# Sheet1.net
KiCad netlist of a schematic drawn in Altium Designer
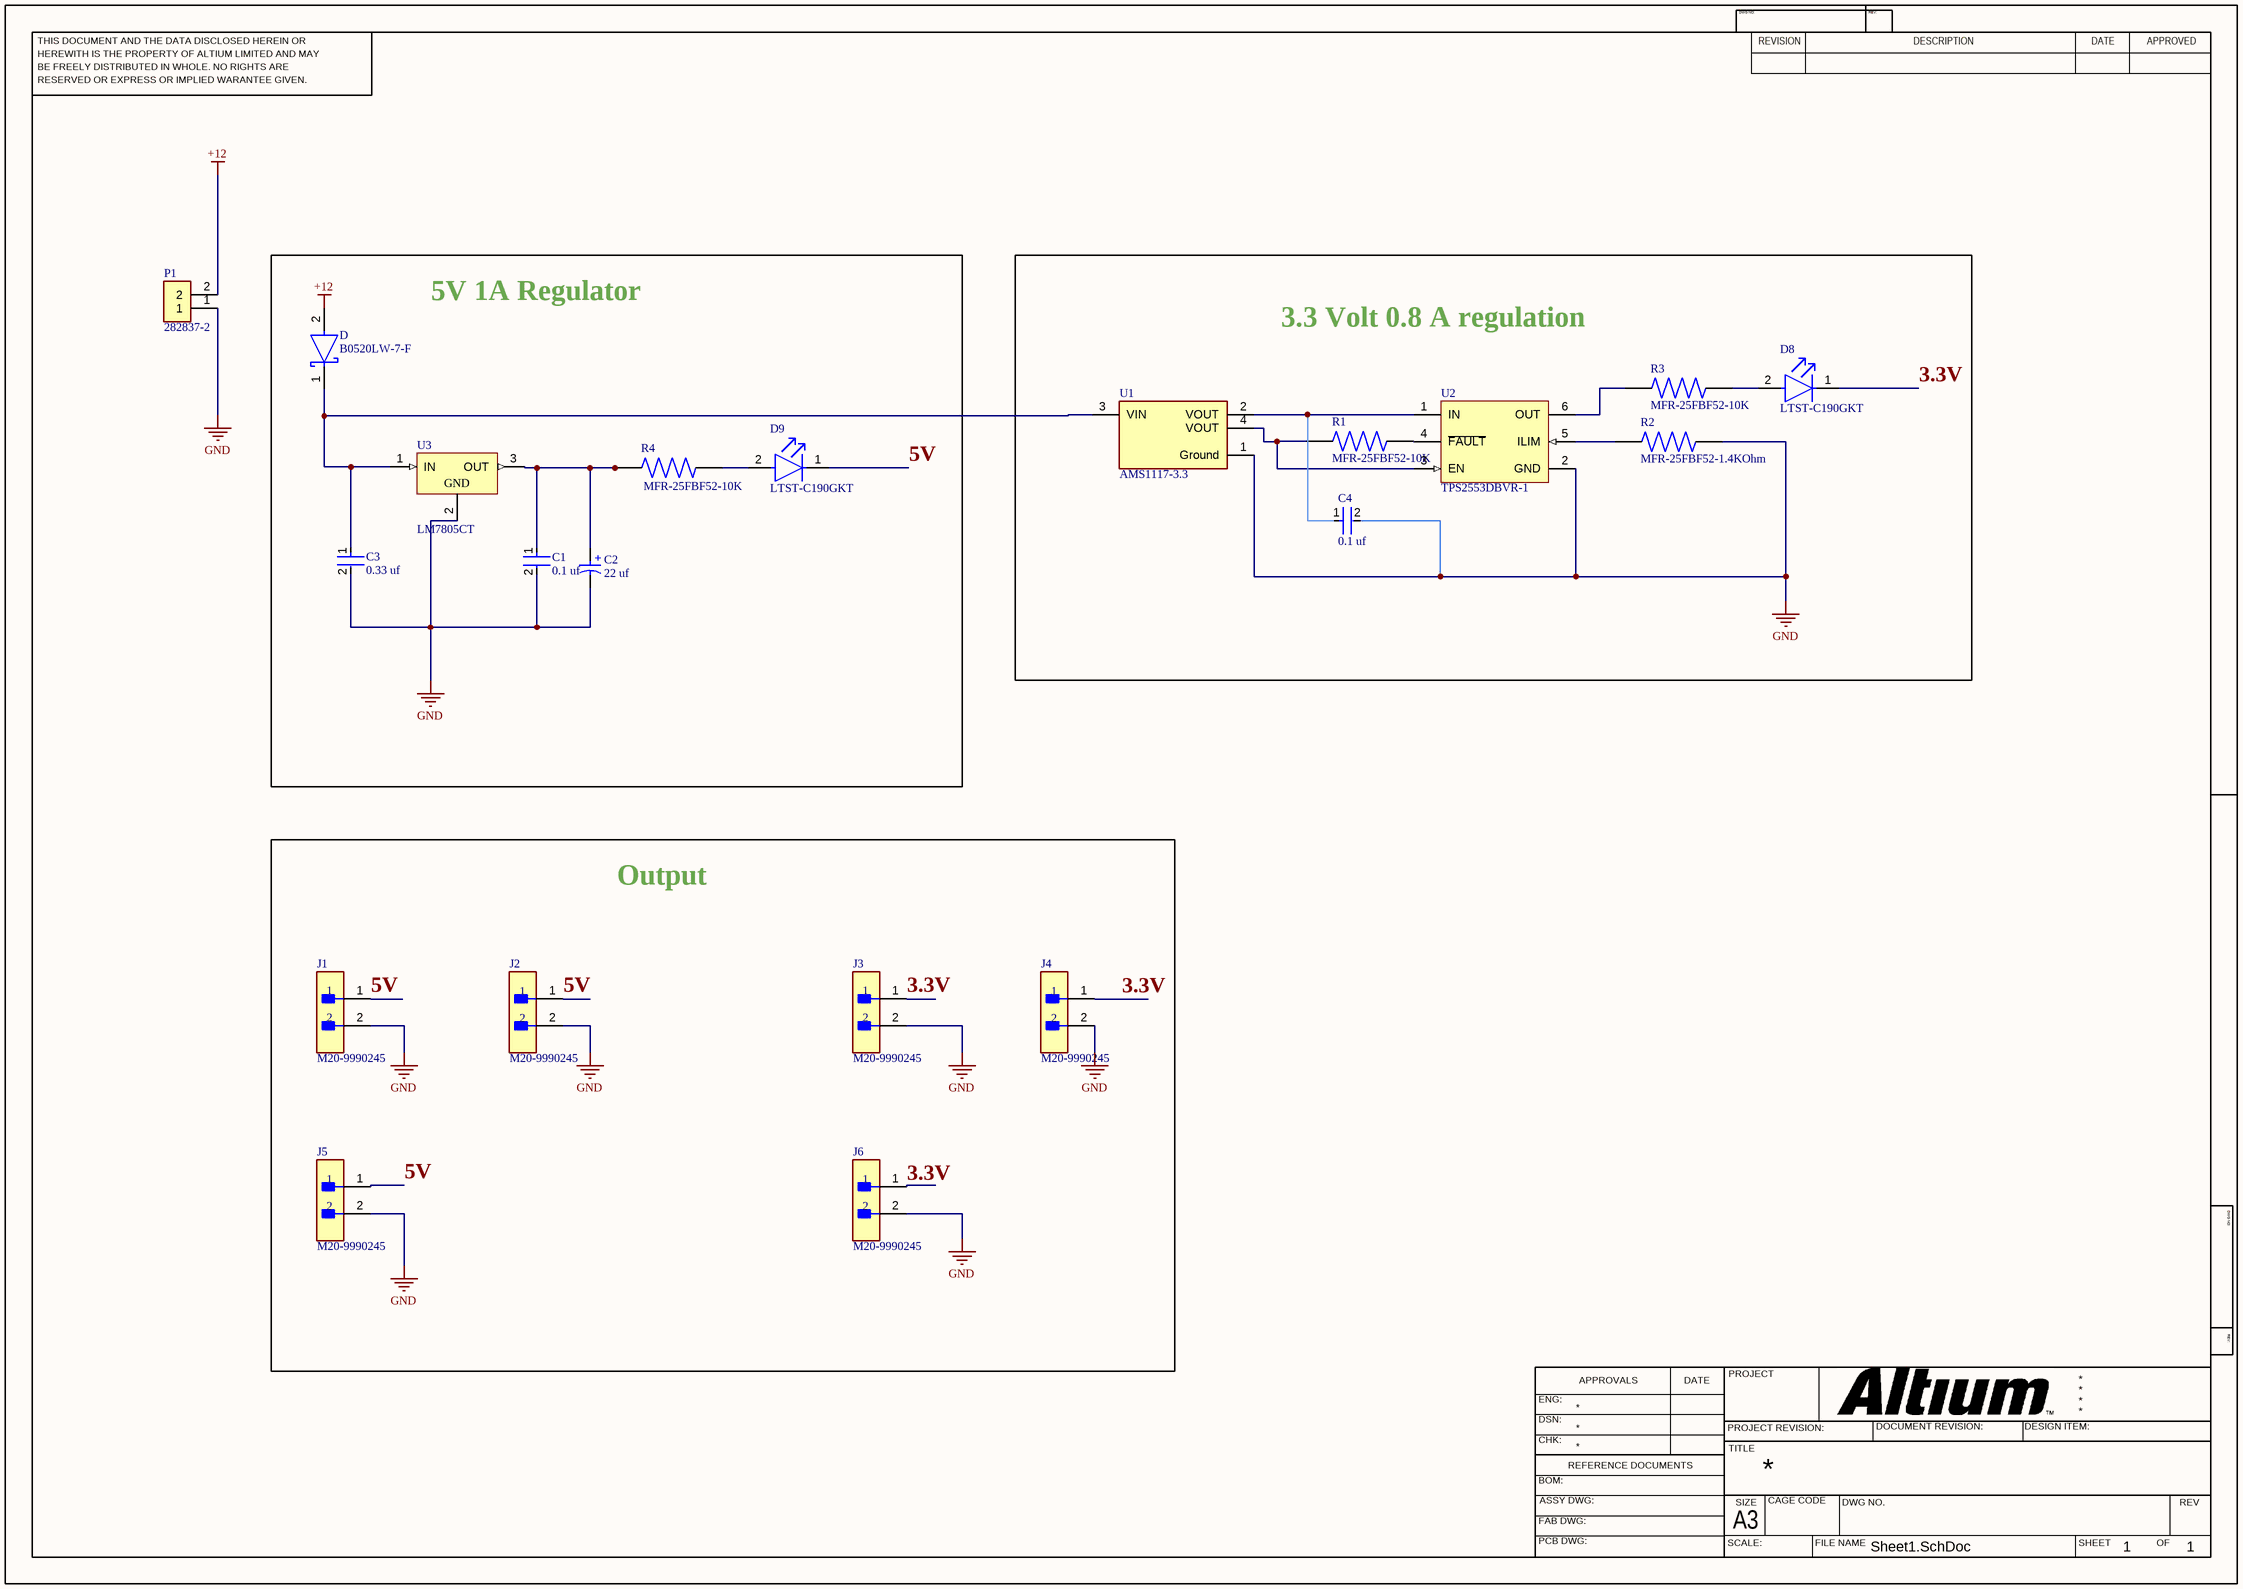
[diagram p0: Sheet1.SchDoc]

(export (version "E")
  (design (tool "Eeschema 10.0.6"))
  (components
    (comp (ref "C1")
      (value "0.1 uf")
      (footprint "FP-CL17-IPC_C")
      (description "Cap Ceramic 100nF 10V X7R ±10% SMD 0402 +125°C Paper T/R")
      (fields (field (name "TOLERANCE") "10%"))
      (libsource (lib "Altium Content Vault") (part "b4654b650e69147ec39a6b967a45e02"))
    )
    (comp (ref "C2")
      (value "22 uf")
      (footprint "WCAP-ASLL_D4H5.5")
      (description "865060240001 WCAP-ASLL Aluminum Electrolytic Capacitors")
      (fields (field (name "TOLERANCE") "20%"))
      (libsource (lib "Altium Content Vault") (part "Capacitor_Polarized"))
    )
    (comp (ref "C3")
      (value "0.33 uf")
      (footprint "FP-GRM31C-0_2-e0_3_0_8-IPC_C")
      (description "CAP CER 0.33UF 25V C0G/NP0 1206")
      (libsource (lib "Altium Content Vault") (part "11868f565c42a9108669ba33697ecf6"))
    )
    (comp (ref "C4")
      (value "0.1 uf")
      (footprint "FP-CL17-IPC_C")
      (description "Cap Ceramic 100nF 10V X7R ±10% SMD 0402 +125°C Paper T/R")
      (fields (field (name "TOLERANCE") "10%"))
      (libsource (lib "Altium Content Vault") (part "b4654b650e69147ec39a6b967a45e02"))
    )
    (comp (ref "D")
      (value "B0520LW-7-F")
      (footprint "FP-SOD123-MFG")
      (description "DIODE SCHOTTKY 20V 500MA SOD123")
      (fields
        (field (name "OCTOPART") "https://octopart.com/b0520lw-7-f-diodes+inc.-325707")
        (field (name "MANUFACTURER") "Diodes Inc.")
      )
      (libsource (lib "Altium Content Vault") (part "1d6ec82d83fb6aee721767c19dac4b9"))
    )
    (comp (ref "D8")
      (value "LTST-C190GKT")
      (footprint "FP-LTST-C190GKT-MFG")
      (description "LED GREEN CLEAR CHIP SMD")
      (fields (field (name "VOLTAGE") "2V"))
      (libsource (lib "Altium Content Vault") (part "8706943c75ba83719d021d2fdc84c58"))
    )
    (comp (ref "D9")
      (value "LTST-C190GKT")
      (footprint "FP-LTST-C190GKT-MFG")
      (description "LED GREEN CLEAR CHIP SMD")
      (fields (field (name "VOLTAGE") "2V"))
      (libsource (lib "Altium Content Vault") (part "8706943c75ba83719d021d2fdc84c58"))
    )
    (comp (ref "J1")
      (value "M20-9990245")
      (footprint "FP-M20-9990245-MFG")
      (description "CONN HEADER VERT 2POS 2.54MM")
      (fields (field (name "VOLTAGE") "50V"))
      (libsource (lib "Altium Content Vault") (part "3bc925449376181038e59eaffc5286c"))
    )
    (comp (ref "J2")
      (value "M20-9990245")
      (footprint "FP-M20-9990245-MFG")
      (description "CONN HEADER VERT 2POS 2.54MM")
      (fields (field (name "VOLTAGE") "50V"))
      (libsource (lib "Altium Content Vault") (part "3bc925449376181038e59eaffc5286c"))
    )
    (comp (ref "J3")
      (value "M20-9990245")
      (footprint "FP-M20-9990245-MFG")
      (description "CONN HEADER VERT 2POS 2.54MM")
      (fields (field (name "VOLTAGE") "50V"))
      (libsource (lib "Altium Content Vault") (part "3bc925449376181038e59eaffc5286c"))
    )
    (comp (ref "J4")
      (value "M20-9990245")
      (footprint "FP-M20-9990245-MFG")
      (description "CONN HEADER VERT 2POS 2.54MM")
      (fields (field (name "VOLTAGE") "50V"))
      (libsource (lib "Altium Content Vault") (part "3bc925449376181038e59eaffc5286c"))
    )
    (comp (ref "J5")
      (value "M20-9990245")
      (footprint "FP-M20-9990245-MFG")
      (description "CONN HEADER VERT 2POS 2.54MM")
      (fields (field (name "VOLTAGE") "50V"))
      (libsource (lib "Altium Content Vault") (part "3bc925449376181038e59eaffc5286c"))
    )
    (comp (ref "J6")
      (value "M20-9990245")
      (footprint "FP-M20-9990245-MFG")
      (description "CONN HEADER VERT 2POS 2.54MM")
      (fields (field (name "VOLTAGE") "50V"))
      (libsource (lib "Altium Content Vault") (part "3bc925449376181038e59eaffc5286c"))
    )
    (comp (ref "P1")
      (value "282837-2")
      (footprint "TE_282837-2")
      (fields (field (name "MF") "TE Connectivity"))
      (libsource (lib "282837-2") (part "282837-2"))
    )
    (comp (ref "R1")
      (value "MFR-25FBF52-10K")
      (footprint "RESAD1100W55L680D260")
      (description "10.2 kOhms Â±1% 0.25W, 1/4W Through Hole Resistor Axial - Metal Film")
      (fields (field (name "MF") "Yageo"))
      (libsource (lib "MFR-25FBF52-10K") (part "MFR-25FBF52-10K"))
    )
    (comp (ref "R2")
      (value "MFR-25FBF52-1.4KOhm")
      (footprint "RESAD1100W55L680D260")
      (description "10.2 kOhms Â±1% 0.25W, 1/4W Through Hole Resistor Axial - Metal Film")
      (fields (field (name "MF") "Yageo") (field (name "MP") "MFR-25FBF52-10K"))
      (libsource (lib "MFR-25FBF52-10K") (part "MFR-25FBF52-10K"))
    )
    (comp (ref "R3")
      (value "MFR-25FBF52-10K")
      (footprint "RESAD1100W55L680D260")
      (description "10.2 kOhms Â±1% 0.25W, 1/4W Through Hole Resistor Axial - Metal Film")
      (fields (field (name "MF") "Yageo"))
      (libsource (lib "MFR-25FBF52-10K") (part "MFR-25FBF52-10K"))
    )
    (comp (ref "R4")
      (value "MFR-25FBF52-10K")
      (footprint "RESAD1100W55L680D260")
      (description "10.2 kOhms Â±1% 0.25W, 1/4W Through Hole Resistor Axial - Metal Film")
      (fields (field (name "MF") "Yageo"))
      (libsource (lib "MFR-25FBF52-10K") (part "MFR-25FBF52-10K"))
    )
    (comp (ref "U1")
      (value "AMS1117-3.3")
      (footprint "FP-AMS1117-IPC_C")
      (description "LDO Voltage Regulators 1A, 3.3V")
      (fields
        (field (name "OCTOPART") "https://octopart.com/ams1117-3.3-advanced+monolithic+systems-25899300")
        (field (name "MANUFACTURER") "Advanced Monolithic Systems")
      )
      (libsource (lib "Altium Content Vault") (part "8bdbb5f8e77002000e30dd2845d0354"))
    )
    (comp (ref "U2")
      (value "TPS2553DBVR-1")
      (footprint "DBV0006A_N")
      (fields (field (name "MANUFACTURER") "Texas Instruments"))
      (libsource (lib "Altium Content Vault") (part "TI-TPS2553-1DBV6"))
    )
    (comp (ref "U3")
      (value "LM7805CT")
      (footprint "FAIR-TO-220-3")
      (description "Positive Voltage Regulator, 5 V, 1 A, -40 to 125 degC, 3-Pin TO-220, RoHS, Tube")
      (fields (field (name "MANUFACTURER") "FairchildSemiconductor"))
      (libsource (lib "Altium Content Vault") (part "FAIR-LM7805CT-TO220-3"))
    )
  )
  (nets
    (net (code "1") (name "+12") (class "Default")
      (node (ref "D") (pin "2") (pinfunction "A_2") (pintype "passive"))
      (node (ref "P1") (pin "2") (pinfunction "2_2") (pintype "passive"))
    )
    (net (code "2") (name "/3.3V") (class "Default")
      (node (ref "D8") (pin "1") (pinfunction "C_1") (pintype "passive"))
      (node (ref "J3") (pin "1") (pinfunction "1_1") (pintype "passive"))
      (node (ref "J4") (pin "1") (pinfunction "1_1") (pintype "passive"))
      (node (ref "J6") (pin "1") (pinfunction "1_1") (pintype "passive"))
    )
    (net (code "3") (name "/5V") (class "Default")
      (node (ref "D9") (pin "1") (pinfunction "C_1") (pintype "passive"))
      (node (ref "J1") (pin "1") (pinfunction "1_1") (pintype "passive"))
      (node (ref "J2") (pin "1") (pinfunction "1_1") (pintype "passive"))
      (node (ref "J5") (pin "1") (pinfunction "1_1") (pintype "passive"))
    )
    (net (code "4") (name "GND") (class "Default")
      (node (ref "C1") (pin "2") (pinfunction "2_2") (pintype "passive"))
      (node (ref "C2") (pin "2") (pinfunction "N_2") (pintype "passive"))
      (node (ref "C3") (pin "2") (pinfunction "2_2") (pintype "passive"))
      (node (ref "C4") (pin "2") (pinfunction "2_2") (pintype "passive"))
      (node (ref "J1") (pin "2") (pinfunction "2_2") (pintype "passive"))
      (node (ref "J2") (pin "2") (pinfunction "2_2") (pintype "passive"))
      (node (ref "J3") (pin "2") (pinfunction "2_2") (pintype "passive"))
      (node (ref "J4") (pin "2") (pinfunction "2_2") (pintype "passive"))
      (node (ref "J5") (pin "2") (pinfunction "2_2") (pintype "passive"))
      (node (ref "J6") (pin "2") (pinfunction "2_2") (pintype "passive"))
      (node (ref "P1") (pin "1") (pinfunction "1_1") (pintype "passive"))
      (node (ref "R2") (pin "2") (pinfunction "2_2") (pintype "passive"))
      (node (ref "U1") (pin "1") (pinfunction "Ground_1") (pintype "power_in"))
      (node (ref "U2") (pin "2") (pinfunction "GND_2") (pintype "power_in"))
      (node (ref "U3") (pin "2") (pinfunction "GND_2") (pintype "power_in"))
    )
    (net (code "5") (name "Net-(C2-P)") (class "Default")
      (node (ref "C1") (pin "1") (pinfunction "1_1") (pintype "passive"))
      (node (ref "C2") (pin "1") (pinfunction "P_1") (pintype "passive"))
      (node (ref "R4") (pin "1") (pinfunction "1_1") (pintype "passive"))
      (node (ref "U3") (pin "3") (pinfunction "OUT_3") (pintype "output"))
    )
    (net (code "6") (name "Net-(D-C)") (class "Default")
      (node (ref "C3") (pin "1") (pinfunction "1_1") (pintype "passive"))
      (node (ref "D") (pin "1") (pinfunction "C_1") (pintype "passive"))
      (node (ref "U1") (pin "3") (pinfunction "VIN_3") (pintype "power_in"))
      (node (ref "U3") (pin "1") (pinfunction "IN_1") (pintype "input"))
    )
    (net (code "7") (name "Net-(D8-A)") (class "Default")
      (node (ref "D8") (pin "2") (pinfunction "A_2") (pintype "passive"))
      (node (ref "R3") (pin "2") (pinfunction "2_2") (pintype "passive"))
    )
    (net (code "8") (name "Net-(D9-A)") (class "Default")
      (node (ref "D9") (pin "2") (pinfunction "A_2") (pintype "passive"))
      (node (ref "R4") (pin "2") (pinfunction "2_2") (pintype "passive"))
    )
    (net (code "9") (name "Net-(U2-EN)") (class "Default")
      (node (ref "R1") (pin "1") (pinfunction "1_1") (pintype "passive"))
      (node (ref "U1") (pin "4") (pinfunction "VOUT_4") (pintype "passive"))
      (node (ref "U2") (pin "3") (pinfunction "EN_3") (pintype "input"))
    )
    (net (code "10") (name "Net-(U2-ILIM)") (class "Default")
      (node (ref "R2") (pin "1") (pinfunction "1_1") (pintype "passive"))
      (node (ref "U2") (pin "5") (pinfunction "ILIM_5") (pintype "input"))
    )
    (net (code "11") (name "Net-(U2-IN)") (class "Default")
      (node (ref "C4") (pin "1") (pinfunction "1_1") (pintype "passive"))
      (node (ref "U1") (pin "2") (pinfunction "VOUT_2") (pintype "passive"))
      (node (ref "U2") (pin "1") (pinfunction "IN_1") (pintype "power_in"))
    )
    (net (code "12") (name "Net-(U2-OUT)") (class "Default")
      (node (ref "R3") (pin "1") (pinfunction "1_1") (pintype "passive"))
      (node (ref "U2") (pin "6") (pinfunction "OUT_6") (pintype "power_in"))
    )
    (net (code "13") (name "Net-(U2-~{FAULT})") (class "Default")
      (node (ref "R1") (pin "2") (pinfunction "2_2") (pintype "passive"))
      (node (ref "U2") (pin "4") (pinfunction "~{FAULT}_4") (pintype "tri_state"))
    )
  )
)
